# GPS_GNSS.net
KiCad netlist of a schematic drawn in Altium Designer
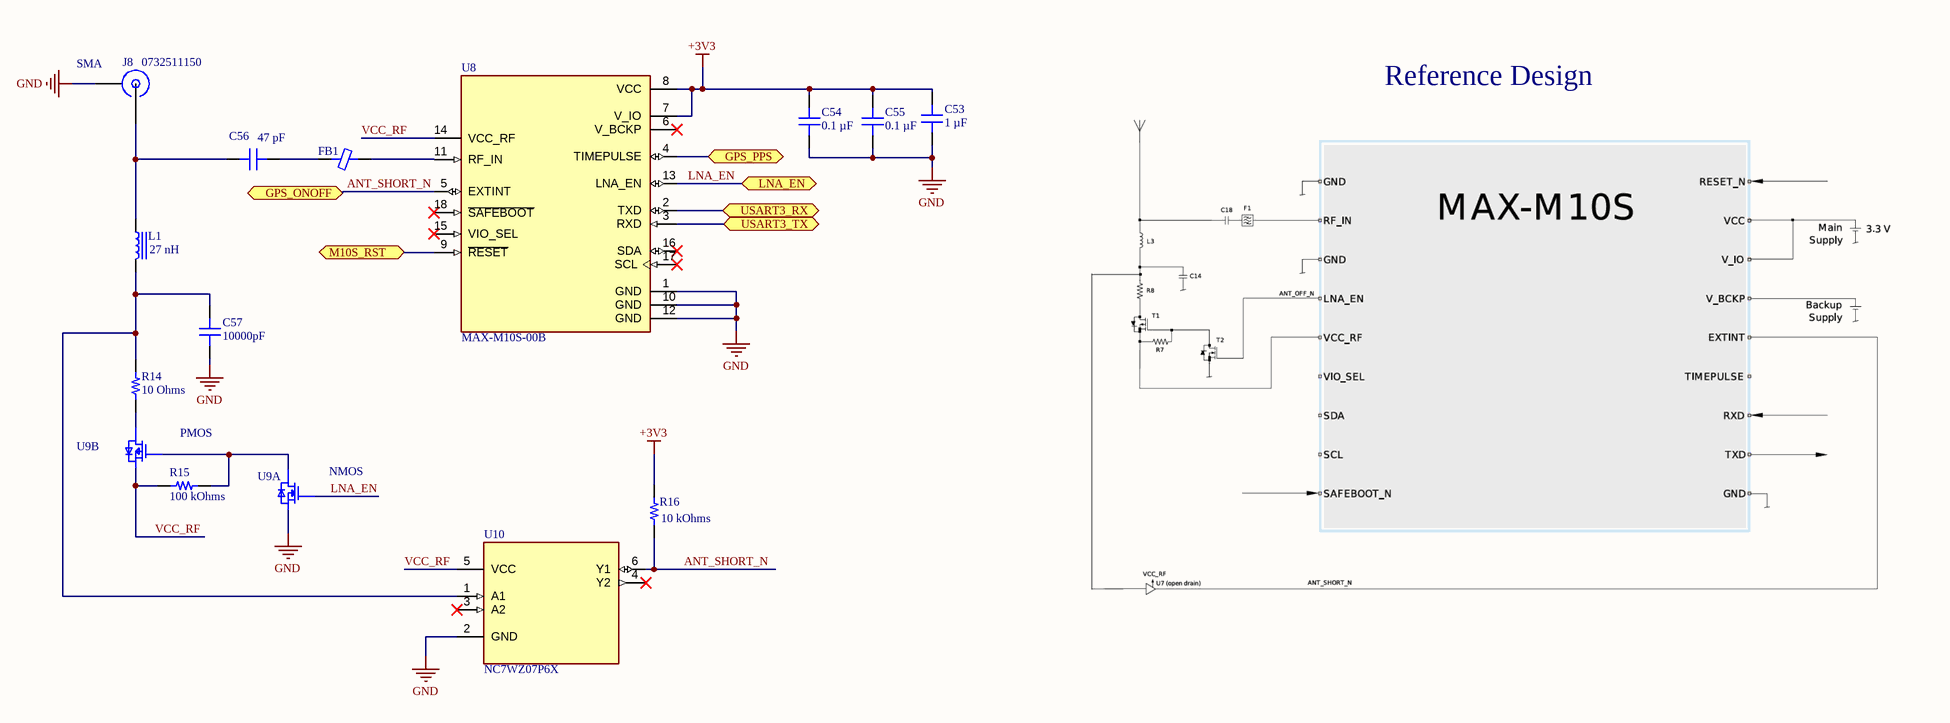
[diagram p0: GPS_GNSS.SchDoc]

(export (version "E")
  (design (tool "Eeschema 10.0.6"))
  (components
    (comp (ref "C53")
      (value "1 µF")
      (footprint "MURATA GRM155 0402_1005")
      (description "CAP CER 1UF 10V X7R 0402")
      (fields
        (field (name "PART NUMBER") "GRM155Z71A105KE01J")
        (field (name "CAPACITANCE") "1 µF")
        (field (name "MANUFACTURER") "Murata Electronics")
      )
      (libsource (lib "Celestial Altium Library - altium_library") (part "Capacitor"))
    )
    (comp (ref "C54")
      (value "0.1 µF")
      (footprint "CAP 0402_1005")
      (description "CAP CER 0.1UF 10V X7R 0402")
      (fields
        (field (name "PART NUMBER") "885012205018")
        (field (name "CAPACITANCE") "0.1 µF")
        (field (name "MANUFACTURER") "Würth Elektronik")
      )
      (libsource (lib "Celestial Altium Library - altium_library") (part "Capacitor"))
    )
    (comp (ref "C55")
      (value "0.1 µF")
      (footprint "CAP 0402_1005")
      (description "CAP CER 0.1UF 10V X7R 0402")
      (fields
        (field (name "PART NUMBER") "885012205018")
        (field (name "CAPACITANCE") "0.1 µF")
        (field (name "MANUFACTURER") "Würth Elektronik")
      )
      (libsource (lib "Celestial Altium Library - altium_library") (part "Capacitor"))
    )
    (comp (ref "C56")
      (value "47 pF")
      (footprint "CAP 0402_1005")
      (description "CAP CER 47PF 25V C0G/NP0 0402")
      (fields
        (field (name "PART NUMBER") "C0402C470J3GACAUTO")
        (field (name "CAPACITANCE") "47 pF")
        (field (name "MANUFACTURER") "KEMET")
      )
      (libsource (lib "Celestial Altium Library - altium_library") (part "Capacitor"))
    )
    (comp (ref "C57")
      (value "10000pF")
      (footprint "CAP 0603_1608 RF")
      (description "CAP CER 10000PF 16V 0603")
      (fields (field (name "PART NUMBER") "EMK107SD103KA-T") (field (name "MANUFACTURER") "Taiyo Yuden"))
      (libsource (lib "Celestial Altium Library - altium_library") (part "Capacitor"))
    )
    (comp (ref "FB1")
      (value "1 kOhms @ 100 MHz")
      (footprint "FER 0402_1005")
      (description "FERRITE BEAD 1K OHM 0402 1LN")
      (fields
        (field (name "PART NUMBER") "BLM15AG102SN1D")
        (field (name "MANUFACTURER") "Murata Electronics")
      )
      (libsource (lib "Celestial Altium Library - altium_library") (part "Ferrite Chip"))
    )
    (comp (ref "J8")
      (value "0732511150")
      (footprint "MOLEX SD-73251-115")
      (description "CONN SMA RCPT STR 50OHM EDGE MNT")
      (fields (field (name "CONNECTOR STYLE") "SMA") (field (name "MANUFACTURER") "Molex"))
      (libsource (lib "Celestial Altium Library - altium_library") (part "COAXIAL JACK"))
    )
    (comp (ref "L1")
      (value "27 nH")
      (footprint "Murata LQG15 0402")
      (description "FIXED IND 27NH 350MA 0.46OHM SMD")
      (fields
        (field (name "PART NUMBER") "LQG15HZ27NJ02D")
        (field (name "MANUFACTURER") "Murata Electronics")
      )
      (libsource (lib "Celestial Altium Library - altium_library") (part "Inductor"))
    )
    (comp (ref "R14")
      (value "10 Ohms")
      (footprint "YAGEO RES 0402_1005")
      (description "RES 10 OHM 5% 1/16W 0402")
      (fields (field (name "PART NUMBER") "RC0402JR-0710RL") (field (name "MANUFACTURER") "Yageo"))
      (libsource (lib "Celestial Altium Library - altium_library") (part "Resistor"))
    )
    (comp (ref "R15")
      (value "100 kOhms")
      (footprint "YAGEO RES 0603_1608")
      (description "RES SMD 100K OHM 1% 1/10W 0603")
      (fields (field (name "PART NUMBER") "AA0603FR-07100KL") (field (name "MANUFACTURER") "Yageo"))
      (libsource (lib "Celestial Altium Library - altium_library") (part "Resistor"))
    )
    (comp (ref "R16")
      (value "10 kOhms")
      (footprint "KOA RES RK73 RN73 0402_1005")
      (description "RES 10K OHM 0.5% 1/10W 0402")
      (fields
        (field (name "PART NUMBER") "RK73H1ETTP1002D")
        (field (name "MANUFACTURER") "KOA Speer Electronics, Inc.")
      )
      (libsource (lib "Celestial Altium Library - altium_library") (part "Resistor"))
    )
    (comp (ref "U8")
      (value "MAX-M10S-00B")
      (footprint "MAX-M10S-00B")
      (fields (field (name "MANUFACTURER") "ublox"))
      (libsource (lib "PCB_Lib") (part "MAX-M10S-00B"))
    )
    (comp (ref "U9")
      (value "DMC2700UDM-7")
      (footprint "SOT-23-6")
      (description "Mosfet Array 20V 1.34A, 1.14A 1.12W Surface Mount SOT-26")
      (fields (field (name "MANUFACTURER") "Diodes Incorporated"))
      (libsource (lib "PCB_Lib") (part "DMC2700UDM-7"))
    )
    (comp (ref "U10")
      (value "NC7WZ07P6X")
      (footprint "NC7WZ07P6X")
      (description "Buffer, Non-Inverting 2 Element 1 Bit per Element Open Drain Output SC-88 (SC-70-6)")
      (fields (field (name "MANUFACTURER") "onsemi"))
      (libsource (lib "PCB_Lib") (part "NC7WZ07P6X"))
    )
  )
  (nets
    (net (code "1") (name "+3V3") (class "Default")
      (node (ref "C53") (pin "2") (pinfunction "2_2") (pintype "passive"))
      (node (ref "C54") (pin "2") (pinfunction "2_2") (pintype "passive"))
      (node (ref "C55") (pin "2") (pinfunction "2_2") (pintype "passive"))
      (node (ref "R16") (pin "1") (pinfunction "1_1") (pintype "passive"))
      (node (ref "U8") (pin "7") (pinfunction "V_IO_7") (pintype "power_in"))
      (node (ref "U8") (pin "8") (pinfunction "VCC_8") (pintype "power_in"))
    )
    (net (code "2") (name "/ANT_SHORT_N") (class "Default")
      (node (ref "R16") (pin "2") (pinfunction "2_2") (pintype "passive"))
      (node (ref "U10") (pin "6") (pinfunction "Y1_6") (pintype "bidirectional"))
      (node (ref "U8") (pin "5") (pinfunction "EXTINT_5") (pintype "bidirectional"))
    )
    (net (code "3") (name "/GPS_PPS") (class "Default")
      (node (ref "U8") (pin "4") (pinfunction "TIMEPULSE_4") (pintype "bidirectional"))
    )
    (net (code "4") (name "/LNA_EN") (class "Default")
      (node (ref "U8") (pin "13") (pinfunction "LNA_EN_13") (pintype "bidirectional"))
      (node (ref "U9") (pin "1") (pinfunction "G1_1") (pintype "passive"))
    )
    (net (code "5") (name "/M10S_RST") (class "Default")
      (node (ref "U8") (pin "9") (pinfunction "~{RESET}_9") (pintype "input"))
    )
    (net (code "6") (name "/USART3_RX") (class "Default")
      (node (ref "U8") (pin "2") (pinfunction "TXD_2") (pintype "bidirectional"))
    )
    (net (code "7") (name "/USART3_TX") (class "Default")
      (node (ref "U8") (pin "3") (pinfunction "RXD_3") (pintype "input"))
    )
    (net (code "8") (name "/VCC_RF") (class "Default")
      (node (ref "R15") (pin "1") (pinfunction "1_1") (pintype "passive"))
      (node (ref "U10") (pin "5") (pinfunction "VCC_5") (pintype "power_in"))
      (node (ref "U8") (pin "14") (pinfunction "VCC_RF_14") (pintype "power_in"))
      (node (ref "U9") (pin "2") (pinfunction "S2_2") (pintype "passive"))
    )
    (net (code "9") (name "GND") (class "Default")
      (node (ref "C53") (pin "1") (pinfunction "1_1") (pintype "passive"))
      (node (ref "C54") (pin "1") (pinfunction "1_1") (pintype "passive"))
      (node (ref "C55") (pin "1") (pinfunction "1_1") (pintype "passive"))
      (node (ref "C57") (pin "2") (pinfunction "2_2") (pintype "passive"))
      (node (ref "J8") (pin "G") (pinfunction "GND_G") (pintype "passive"))
      (node (ref "U10") (pin "2") (pinfunction "GND_2") (pintype "passive"))
      (node (ref "U8") (pin "1") (pinfunction "GND_1") (pintype "power_in"))
      (node (ref "U8") (pin "10") (pinfunction "GND_10") (pintype "power_in"))
      (node (ref "U8") (pin "12") (pinfunction "GND_12") (pintype "power_in"))
      (node (ref "U9") (pin "5") (pinfunction "S1_5") (pintype "passive"))
    )
    (net (code "10") (name "Net-(C56-Pad2)") (class "Default")
      (node (ref "C56") (pin "2") (pinfunction "2_2") (pintype "passive"))
      (node (ref "FB1") (pin "1") (pinfunction "1_1") (pintype "passive"))
    )
    (net (code "11") (name "Net-(J8-SIGNAL)") (class "Default")
      (node (ref "C56") (pin "1") (pinfunction "1_1") (pintype "passive"))
      (node (ref "J8") (pin "S") (pinfunction "SIGNAL_S") (pintype "passive"))
      (node (ref "L1") (pin "1") (pinfunction "1_1") (pintype "passive"))
    )
    (net (code "12") (name "Net-(U8-RF_IN)") (class "Default")
      (node (ref "FB1") (pin "2") (pinfunction "2_2") (pintype "passive"))
      (node (ref "U8") (pin "11") (pinfunction "RF_IN_11") (pintype "input"))
    )
    (net (code "13") (name "Net-(U9A-D1)") (class "Default")
      (node (ref "R15") (pin "2") (pinfunction "2_2") (pintype "passive"))
      (node (ref "U9") (pin "3") (pinfunction "G2_3") (pintype "passive"))
      (node (ref "U9") (pin "6") (pinfunction "D1_6") (pintype "passive"))
    )
    (net (code "14") (name "Net-(U9B-D2)") (class "Default")
      (node (ref "R14") (pin "1") (pinfunction "1_1") (pintype "passive"))
      (node (ref "U9") (pin "4") (pinfunction "D2_4") (pintype "passive"))
    )
    (net (code "15") (name "Net-(U10-A1)") (class "Default")
      (node (ref "C57") (pin "1") (pinfunction "1_1") (pintype "passive"))
      (node (ref "L1") (pin "2") (pinfunction "2_2") (pintype "passive"))
      (node (ref "R14") (pin "2") (pinfunction "2_2") (pintype "passive"))
      (node (ref "U10") (pin "1") (pinfunction "A1_1") (pintype "input"))
    )
    (net (code "16") (name "unconnected-(U8-SCL-Pad17)") (class "Default")
      (node (ref "U8") (pin "17") (pinfunction "SCL_17") (pintype "input+no_connect"))
    )
    (net (code "17") (name "unconnected-(U8-SDA-Pad16)") (class "Default")
      (node (ref "U8") (pin "16") (pinfunction "SDA_16") (pintype "bidirectional+no_connect"))
    )
    (net (code "18") (name "unconnected-(U8-VIO_SEL-Pad15)") (class "Default")
      (node (ref "U8") (pin "15") (pinfunction "VIO_SEL_15") (pintype "input+no_connect"))
    )
    (net (code "19") (name "unconnected-(U8-V_BCKP-Pad6)") (class "Default")
      (node (ref "U8") (pin "6") (pinfunction "V_BCKP_6") (pintype "power_in+no_connect"))
    )
    (net (code "20") (name "unconnected-(U8-~{SAFEBOOT}-Pad18)") (class "Default")
      (node (ref "U8") (pin "18") (pinfunction "~{SAFEBOOT}_18") (pintype "input+no_connect"))
    )
    (net (code "21") (name "unconnected-(U10-A2-Pad3)") (class "Default")
      (node (ref "U10") (pin "3") (pinfunction "A2_3") (pintype "input+no_connect"))
    )
    (net (code "22") (name "unconnected-(U10-Y2-Pad4)") (class "Default")
      (node (ref "U10") (pin "4") (pinfunction "Y2_4") (pintype "output+no_connect"))
    )
  )
)
